# transceiver-AX5043-v1.net
KiCad netlist of a schematic drawn in EAGLE
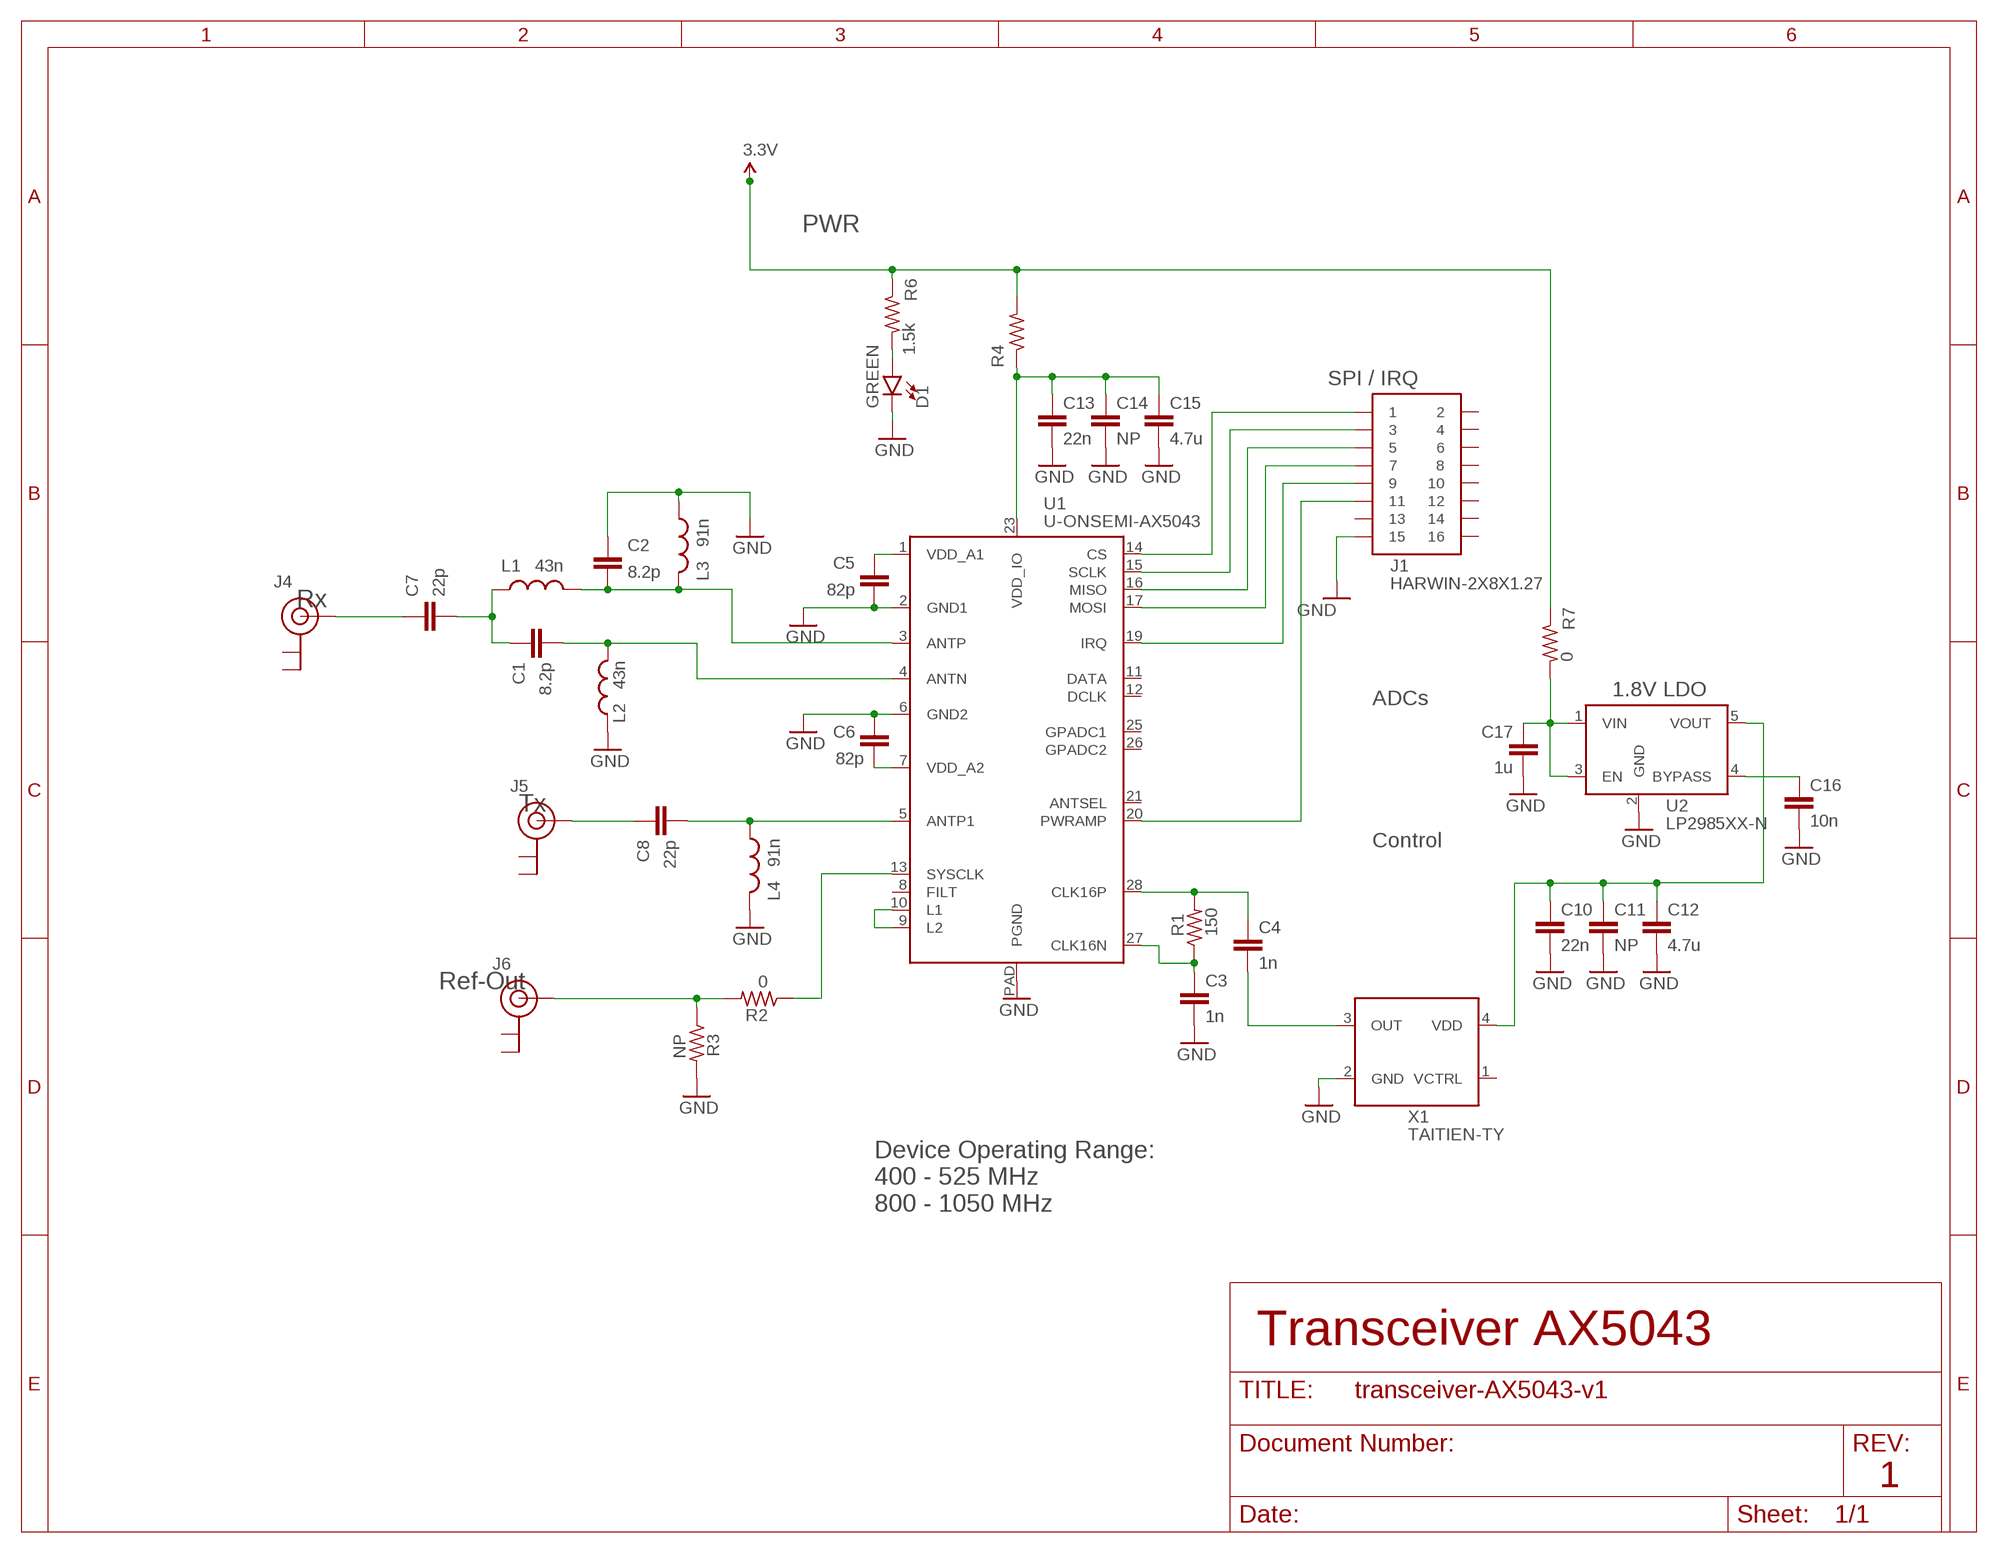
[diagram p0: schematic, sheet 1]

(export (version "E")
  (design (tool "Eeschema 10.0.6"))
  (components
    (comp (ref "C1")
      (value "8.2p")
      (footprint "eagle-import:.0402-C-NOSILK")
      (libsource (lib "eagle-import") (part "C-EU0402-C-NOSILK"))
    )
    (comp (ref "C2")
      (value "8.2p")
      (footprint "eagle-import:.0402-C-NOSILK")
      (libsource (lib "eagle-import") (part "C-EU0402-C-NOSILK"))
    )
    (comp (ref "C3")
      (value "1n")
      (footprint "eagle-import:.0402-C-NOSILK")
      (libsource (lib "eagle-import") (part "C-EU0402-C-NOSILK"))
    )
    (comp (ref "C4")
      (value "1n")
      (footprint "eagle-import:.0402-C-NOSILK")
      (libsource (lib "eagle-import") (part "C-EU0402-C-NOSILK"))
    )
    (comp (ref "C5")
      (value "82p")
      (footprint "eagle-import:.0402-C-NOSILK")
      (libsource (lib "eagle-import") (part "C-EU0402-C-NOSILK"))
    )
    (comp (ref "C6")
      (value "82p")
      (footprint "eagle-import:.0402-C-NOSILK")
      (libsource (lib "eagle-import") (part "C-EU0402-C-NOSILK"))
    )
    (comp (ref "C7")
      (value "22p")
      (footprint "eagle-import:.0402-C-NOSILK")
      (libsource (lib "eagle-import") (part "C-EU0402-C-NOSILK"))
    )
    (comp (ref "C8")
      (value "22p")
      (footprint "eagle-import:.0402-C-NOSILK")
      (libsource (lib "eagle-import") (part "C-EU0402-C-NOSILK"))
    )
    (comp (ref "C10")
      (value "22n")
      (footprint "eagle-import:.0603-C-NOSILK")
      (libsource (lib "eagle-import") (part "C-EU0603-C-NOSILK"))
    )
    (comp (ref "C11")
      (value "NP")
      (footprint "eagle-import:.0603-C-NOSILK")
      (libsource (lib "eagle-import") (part "C-EU0603-C-NOSILK"))
    )
    (comp (ref "C12")
      (value "4.7u")
      (footprint "eagle-import:.0603-C-NOSILK")
      (libsource (lib "eagle-import") (part "C-EU0603-C-NOSILK"))
    )
    (comp (ref "C13")
      (value "22n")
      (footprint "eagle-import:.0603-C-NOSILK")
      (libsource (lib "eagle-import") (part "C-EU0603-C-NOSILK"))
    )
    (comp (ref "C14")
      (value "NP")
      (footprint "eagle-import:.0603-C-NOSILK")
      (libsource (lib "eagle-import") (part "C-EU0603-C-NOSILK"))
    )
    (comp (ref "C15")
      (value "4.7u")
      (footprint "eagle-import:.0603-C-NOSILK")
      (libsource (lib "eagle-import") (part "C-EU0603-C-NOSILK"))
    )
    (comp (ref "C16")
      (value "10n")
      (footprint "eagle-import:.0603-C-NOSILK")
      (libsource (lib "eagle-import") (part "C-EU0603-C-NOSILK"))
    )
    (comp (ref "C17")
      (value "1u")
      (footprint "eagle-import:.0603-C-NOSILK")
      (libsource (lib "eagle-import") (part "C-EU0603-C-NOSILK"))
    )
    (comp (ref "D1")
      (value "GREEN")
      (footprint "eagle-import:LED-0603")
      (libsource (lib "eagle-import") (part "LED-GREEN0603"))
    )
    (comp (ref "J1")
      (value "HARWIN-2X8X1.27")
      (footprint "eagle-import:2X8X1.27")
      (libsource (lib "eagle-import") (part "HARWIN-2X8X1.27"))
    )
    (comp (ref "J4")
      (value "U.FL")
      (footprint "eagle-import:U.FL")
      (libsource (lib "eagle-import") (part "U.FL"))
    )
    (comp (ref "J5")
      (value "U.FL")
      (footprint "eagle-import:U.FL")
      (libsource (lib "eagle-import") (part "U.FL"))
    )
    (comp (ref "J6")
      (value "U.FL")
      (footprint "eagle-import:U.FL")
      (libsource (lib "eagle-import") (part "U.FL"))
    )
    (comp (ref "L1")
      (value "43n")
      (footprint "eagle-import:.0402-C-NOSILK")
      (libsource (lib "eagle-import") (part "L-US0402-C-NOSILK"))
    )
    (comp (ref "L2")
      (value "43n")
      (footprint "eagle-import:.0402-C-NOSILK")
      (libsource (lib "eagle-import") (part "L-US0402-C-NOSILK"))
    )
    (comp (ref "L3")
      (value "91n")
      (footprint "eagle-import:.0603-C-NOSILK")
      (libsource (lib "eagle-import") (part "L-US0603-C-NOSILK"))
    )
    (comp (ref "L4")
      (value "91n")
      (footprint "eagle-import:.0603-C-NOSILK")
      (libsource (lib "eagle-import") (part "L-US0603-C-NOSILK"))
    )
    (comp (ref "R1")
      (value "150")
      (footprint "eagle-import:.0402-C-NOSILK")
      (libsource (lib "eagle-import") (part "R-US_0402-C-NOSILK"))
    )
    (comp (ref "R2")
      (value "0")
      (footprint "eagle-import:.0402-C-NOSILK")
      (libsource (lib "eagle-import") (part "R-US_0402-C-NOSILK"))
    )
    (comp (ref "R3")
      (value "NP")
      (footprint "eagle-import:.0402-C-NOSILK")
      (libsource (lib "eagle-import") (part "R-US_0402-C-NOSILK"))
    )
    (comp (ref "R4")
      (value "0")
      (footprint "eagle-import:.0603-C-NOSILK")
      (libsource (lib "eagle-import") (part "R-US_0603-C-NOSILK"))
    )
    (comp (ref "R6")
      (value "1.5k")
      (footprint "eagle-import:.0603-B-NOSILK")
      (libsource (lib "eagle-import") (part "R-US_0603-B-NOSILK"))
    )
    (comp (ref "R7")
      (value "0")
      (footprint "eagle-import:.0603-C-NOSILK")
      (libsource (lib "eagle-import") (part "R-US_0603-C-NOSILK"))
    )
    (comp (ref "U1")
      (value "U-ONSEMI-AX5043")
      (footprint "eagle-import:QFN28-5X5-WITH-CENTER-PAD")
      (libsource (lib "eagle-import") (part "U-ONSEMI-AX5043"))
    )
    (comp (ref "U2")
      (value "LP2985XX-N")
      (footprint "eagle-import:SOT-23")
      (libsource (lib "eagle-import") (part "LP2985XX-N"))
    )
    (comp (ref "X1")
      (value "TAITIEN-TY")
      (footprint "eagle-import:2.5X2.0")
      (libsource (lib "eagle-import") (part "TAITIEN-TY"))
    )
  )
  (nets
    (net (code "1") (name "3.3V") (class "Default")
      (node (ref "C13") (pin "1") (pinfunction "1_1") (pintype "passive"))
      (node (ref "C14") (pin "1") (pinfunction "1_1") (pintype "passive"))
      (node (ref "C15") (pin "1") (pinfunction "1_1") (pintype "passive"))
      (node (ref "C17") (pin "1") (pinfunction "1_1") (pintype "passive"))
      (node (ref "R4") (pin "1") (pinfunction "1_1") (pintype "passive"))
      (node (ref "R4") (pin "2") (pinfunction "2_2") (pintype "passive"))
      (node (ref "R6") (pin "1") (pinfunction "1_1") (pintype "passive"))
      (node (ref "R7") (pin "1") (pinfunction "1_1") (pintype "passive"))
      (node (ref "R7") (pin "2") (pinfunction "2_2") (pintype "passive"))
      (node (ref "U1") (pin "23") (pinfunction "VDD_IO_23") (pintype "power_in"))
      (node (ref "U2") (pin "1") (pinfunction "VIN_1") (pintype "power_in"))
      (node (ref "U2") (pin "3") (pinfunction "EN_3") (pintype "input"))
    )
    (net (code "2") (name "GND") (class "Default")
      (node (ref "C10") (pin "2") (pinfunction "2_2") (pintype "passive"))
      (node (ref "C11") (pin "2") (pinfunction "2_2") (pintype "passive"))
      (node (ref "C12") (pin "2") (pinfunction "2_2") (pintype "passive"))
      (node (ref "C13") (pin "2") (pinfunction "2_2") (pintype "passive"))
      (node (ref "C14") (pin "2") (pinfunction "2_2") (pintype "passive"))
      (node (ref "C15") (pin "2") (pinfunction "2_2") (pintype "passive"))
      (node (ref "C16") (pin "2") (pinfunction "2_2") (pintype "passive"))
      (node (ref "C17") (pin "2") (pinfunction "2_2") (pintype "passive"))
      (node (ref "C2") (pin "1") (pinfunction "1_1") (pintype "passive"))
      (node (ref "C3") (pin "2") (pinfunction "2_2") (pintype "passive"))
      (node (ref "C5") (pin "2") (pinfunction "2_2") (pintype "passive"))
      (node (ref "C6") (pin "1") (pinfunction "1_1") (pintype "passive"))
      (node (ref "D1") (pin "C") (pinfunction "C_C") (pintype "passive"))
      (node (ref "J1") (pin "15") (pinfunction "15_15") (pintype "passive"))
      (node (ref "L2") (pin "1") (pinfunction "1_1") (pintype "passive"))
      (node (ref "L3") (pin "2") (pinfunction "2_2") (pintype "passive"))
      (node (ref "L4") (pin "1") (pinfunction "1_1") (pintype "passive"))
      (node (ref "R3") (pin "2") (pinfunction "2_2") (pintype "passive"))
      (node (ref "U1") (pin "2") (pinfunction "GND1_2") (pintype "power_in"))
      (node (ref "U1") (pin "6") (pinfunction "GND2_6") (pintype "power_in"))
      (node (ref "U1") (pin "PAD") (pinfunction "PGND_PAD") (pintype "power_in"))
      (node (ref "U2") (pin "2") (pinfunction "GND_2") (pintype "power_in"))
      (node (ref "X1") (pin "2") (pinfunction "GND_2") (pintype "power_in"))
    )
    (net (code "3") (name "Net-(C1-Pad1)") (class "Default")
      (node (ref "C1") (pin "1") (pinfunction "1_1") (pintype "passive"))
      (node (ref "C7") (pin "2") (pinfunction "2_2") (pintype "passive"))
      (node (ref "L1") (pin "1") (pinfunction "1_1") (pintype "passive"))
    )
    (net (code "4") (name "Net-(D1-PadA)") (class "Default")
      (node (ref "D1") (pin "A") (pinfunction "A_A") (pintype "passive"))
      (node (ref "R6") (pin "2") (pinfunction "2_2") (pintype "passive"))
    )
    (net (code "5") (name "Net-(J4-SIGNAL)") (class "Default")
      (node (ref "C7") (pin "1") (pinfunction "1_1") (pintype "passive"))
      (node (ref "J4") (pin "FEED") (pinfunction "SIGNAL_FEED") (pintype "bidirectional"))
    )
    (net (code "6") (name "Net-(J5-SIGNAL)") (class "Default")
      (node (ref "C8") (pin "1") (pinfunction "1_1") (pintype "passive"))
      (node (ref "J5") (pin "FEED") (pinfunction "SIGNAL_FEED") (pintype "bidirectional"))
    )
    (net (code "7") (name "Net-(J6-SIGNAL)") (class "Default")
      (node (ref "J6") (pin "FEED") (pinfunction "SIGNAL_FEED") (pintype "bidirectional"))
      (node (ref "R2") (pin "2") (pinfunction "2_2") (pintype "passive"))
      (node (ref "R3") (pin "1") (pinfunction "1_1") (pintype "passive"))
    )
    (net (code "8") (name "Net-(U1-ANTN)") (class "Default")
      (node (ref "C1") (pin "2") (pinfunction "2_2") (pintype "passive"))
      (node (ref "L2") (pin "2") (pinfunction "2_2") (pintype "passive"))
      (node (ref "U1") (pin "4") (pinfunction "ANTN_4") (pintype "bidirectional"))
    )
    (net (code "9") (name "Net-(U1-ANTP)") (class "Default")
      (node (ref "C2") (pin "2") (pinfunction "2_2") (pintype "passive"))
      (node (ref "L1") (pin "2") (pinfunction "2_2") (pintype "passive"))
      (node (ref "L3") (pin "1") (pinfunction "1_1") (pintype "passive"))
      (node (ref "U1") (pin "3") (pinfunction "ANTP_3") (pintype "bidirectional"))
    )
    (net (code "10") (name "Net-(U1-ANTP1)") (class "Default")
      (node (ref "C8") (pin "2") (pinfunction "2_2") (pintype "passive"))
      (node (ref "L4") (pin "2") (pinfunction "2_2") (pintype "passive"))
      (node (ref "U1") (pin "5") (pinfunction "ANTP1_5") (pintype "bidirectional"))
    )
    (net (code "11") (name "Net-(U1-CLK16N)") (class "Default")
      (node (ref "C3") (pin "1") (pinfunction "1_1") (pintype "passive"))
      (node (ref "R1") (pin "1") (pinfunction "1_1") (pintype "passive"))
      (node (ref "U1") (pin "27") (pinfunction "CLK16N_27") (pintype "passive"))
    )
    (net (code "12") (name "Net-(U1-CLK16P)") (class "Default")
      (node (ref "C4") (pin "1") (pinfunction "1_1") (pintype "passive"))
      (node (ref "R1") (pin "2") (pinfunction "2_2") (pintype "passive"))
      (node (ref "U1") (pin "28") (pinfunction "CLK16P_28") (pintype "passive"))
    )
    (net (code "13") (name "Net-(U1-CS)") (class "Default")
      (node (ref "J1") (pin "1") (pinfunction "1_1") (pintype "passive"))
      (node (ref "U1") (pin "14") (pinfunction "CS_14") (pintype "input"))
    )
    (net (code "14") (name "Net-(U1-IRQ)") (class "Default")
      (node (ref "J1") (pin "9") (pinfunction "9_9") (pintype "passive"))
      (node (ref "U1") (pin "19") (pinfunction "IRQ_19") (pintype "bidirectional"))
    )
    (net (code "15") (name "Net-(U1-L1)") (class "Default")
      (node (ref "U1") (pin "10") (pinfunction "L1_10") (pintype "input"))
      (node (ref "U1") (pin "9") (pinfunction "L2_9") (pintype "input"))
    )
    (net (code "16") (name "Net-(U1-MISO)") (class "Default")
      (node (ref "J1") (pin "5") (pinfunction "5_5") (pintype "passive"))
      (node (ref "U1") (pin "16") (pinfunction "MISO_16") (pintype "output"))
    )
    (net (code "17") (name "Net-(U1-MOSI)") (class "Default")
      (node (ref "J1") (pin "7") (pinfunction "7_7") (pintype "passive"))
      (node (ref "U1") (pin "17") (pinfunction "MOSI_17") (pintype "input"))
    )
    (net (code "18") (name "Net-(U1-PWRAMP)") (class "Default")
      (node (ref "J1") (pin "11") (pinfunction "11_11") (pintype "passive"))
      (node (ref "U1") (pin "20") (pinfunction "PWRAMP_20") (pintype "bidirectional"))
    )
    (net (code "19") (name "Net-(U1-SCLK)") (class "Default")
      (node (ref "J1") (pin "3") (pinfunction "3_3") (pintype "passive"))
      (node (ref "U1") (pin "15") (pinfunction "SCLK_15") (pintype "input"))
    )
    (net (code "20") (name "Net-(U1-SYSCLK)") (class "Default")
      (node (ref "R2") (pin "1") (pinfunction "1_1") (pintype "passive"))
      (node (ref "U1") (pin "13") (pinfunction "SYSCLK_13") (pintype "bidirectional"))
    )
    (net (code "21") (name "Net-(U1-VDD_A1)") (class "Default")
      (node (ref "C5") (pin "1") (pinfunction "1_1") (pintype "passive"))
      (node (ref "U1") (pin "1") (pinfunction "VDD_A1_1") (pintype "power_in"))
    )
    (net (code "22") (name "Net-(U1-VDD_A2)") (class "Default")
      (node (ref "C6") (pin "2") (pinfunction "2_2") (pintype "passive"))
      (node (ref "U1") (pin "7") (pinfunction "VDD_A2_7") (pintype "power_in"))
    )
    (net (code "23") (name "Net-(U2-BYPASS)") (class "Default")
      (node (ref "C16") (pin "1") (pinfunction "1_1") (pintype "passive"))
      (node (ref "U2") (pin "4") (pinfunction "BYPASS_4") (pintype "power_in"))
    )
    (net (code "24") (name "Net-(U2-VOUT)") (class "Default")
      (node (ref "C10") (pin "1") (pinfunction "1_1") (pintype "passive"))
      (node (ref "C11") (pin "1") (pinfunction "1_1") (pintype "passive"))
      (node (ref "C12") (pin "1") (pinfunction "1_1") (pintype "passive"))
      (node (ref "U2") (pin "5") (pinfunction "VOUT_5") (pintype "power_in"))
      (node (ref "X1") (pin "4") (pinfunction "VDD_4") (pintype "power_in"))
    )
    (net (code "25") (name "Net-(X1-OUT)") (class "Default")
      (node (ref "C4") (pin "2") (pinfunction "2_2") (pintype "passive"))
      (node (ref "X1") (pin "3") (pinfunction "OUT_3") (pintype "output"))
    )
    (net (code "26") (name "unconnected-(J1-Pad2)") (class "Default")
      (node (ref "J1") (pin "2") (pinfunction "2_2") (pintype "passive"))
    )
    (net (code "27") (name "unconnected-(J1-Pad4)") (class "Default")
      (node (ref "J1") (pin "4") (pinfunction "4_4") (pintype "passive"))
    )
    (net (code "28") (name "unconnected-(J1-Pad6)") (class "Default")
      (node (ref "J1") (pin "6") (pinfunction "6_6") (pintype "passive"))
    )
    (net (code "29") (name "unconnected-(J1-Pad8)") (class "Default")
      (node (ref "J1") (pin "8") (pinfunction "8_8") (pintype "passive"))
    )
    (net (code "30") (name "unconnected-(J1-Pad10)") (class "Default")
      (node (ref "J1") (pin "10") (pinfunction "10_10") (pintype "passive"))
    )
    (net (code "31") (name "unconnected-(J1-Pad12)") (class "Default")
      (node (ref "J1") (pin "12") (pinfunction "12_12") (pintype "passive"))
    )
    (net (code "32") (name "unconnected-(J1-Pad13)") (class "Default")
      (node (ref "J1") (pin "13") (pinfunction "13_13") (pintype "passive"))
    )
    (net (code "33") (name "unconnected-(J1-Pad14)") (class "Default")
      (node (ref "J1") (pin "14") (pinfunction "14_14") (pintype "passive"))
    )
    (net (code "34") (name "unconnected-(J1-Pad16)") (class "Default")
      (node (ref "J1") (pin "16") (pinfunction "16_16") (pintype "passive"))
    )
    (net (code "35") (name "unconnected-(J4-GND-Pad1)") (class "Default")
      (node (ref "J4") (pin "1") (pinfunction "GND_1") (pintype "bidirectional"))
    )
    (net (code "36") (name "unconnected-(J4-GND-Pad2)") (class "Default")
      (node (ref "J4") (pin "2") (pinfunction "GND_2") (pintype "bidirectional"))
    )
    (net (code "37") (name "unconnected-(J5-GND-Pad1)") (class "Default")
      (node (ref "J5") (pin "1") (pinfunction "GND_1") (pintype "bidirectional"))
    )
    (net (code "38") (name "unconnected-(J5-GND-Pad2)") (class "Default")
      (node (ref "J5") (pin "2") (pinfunction "GND_2") (pintype "bidirectional"))
    )
    (net (code "39") (name "unconnected-(J6-GND-Pad1)") (class "Default")
      (node (ref "J6") (pin "1") (pinfunction "GND_1") (pintype "bidirectional"))
    )
    (net (code "40") (name "unconnected-(J6-GND-Pad2)") (class "Default")
      (node (ref "J6") (pin "2") (pinfunction "GND_2") (pintype "bidirectional"))
    )
    (net (code "41") (name "unconnected-(U1-ANTSEL-Pad21)") (class "Default")
      (node (ref "U1") (pin "21") (pinfunction "ANTSEL_21") (pintype "bidirectional"))
    )
    (net (code "42") (name "unconnected-(U1-DATA-Pad11)") (class "Default")
      (node (ref "U1") (pin "11") (pinfunction "DATA_11") (pintype "bidirectional"))
    )
    (net (code "43") (name "unconnected-(U1-DCLK-Pad12)") (class "Default")
      (node (ref "U1") (pin "12") (pinfunction "DCLK_12") (pintype "bidirectional"))
    )
    (net (code "44") (name "unconnected-(U1-FILT-Pad8)") (class "Default")
      (node (ref "U1") (pin "8") (pinfunction "FILT_8") (pintype "output"))
    )
    (net (code "45") (name "unconnected-(U1-GPADC1-Pad25)") (class "Default")
      (node (ref "U1") (pin "25") (pinfunction "GPADC1_25") (pintype "input"))
    )
    (net (code "46") (name "unconnected-(U1-GPADC2-Pad26)") (class "Default")
      (node (ref "U1") (pin "26") (pinfunction "GPADC2_26") (pintype "input"))
    )
    (net (code "47") (name "unconnected-(X1-VCTRL-Pad1)") (class "Default")
      (node (ref "X1") (pin "1") (pinfunction "VCTRL_1") (pintype "input"))
    )
  )
)
